# MelansonTech_Isolated_Shunt_Amplifier.net
KiCad netlist of a schematic drawn in Altium Designer
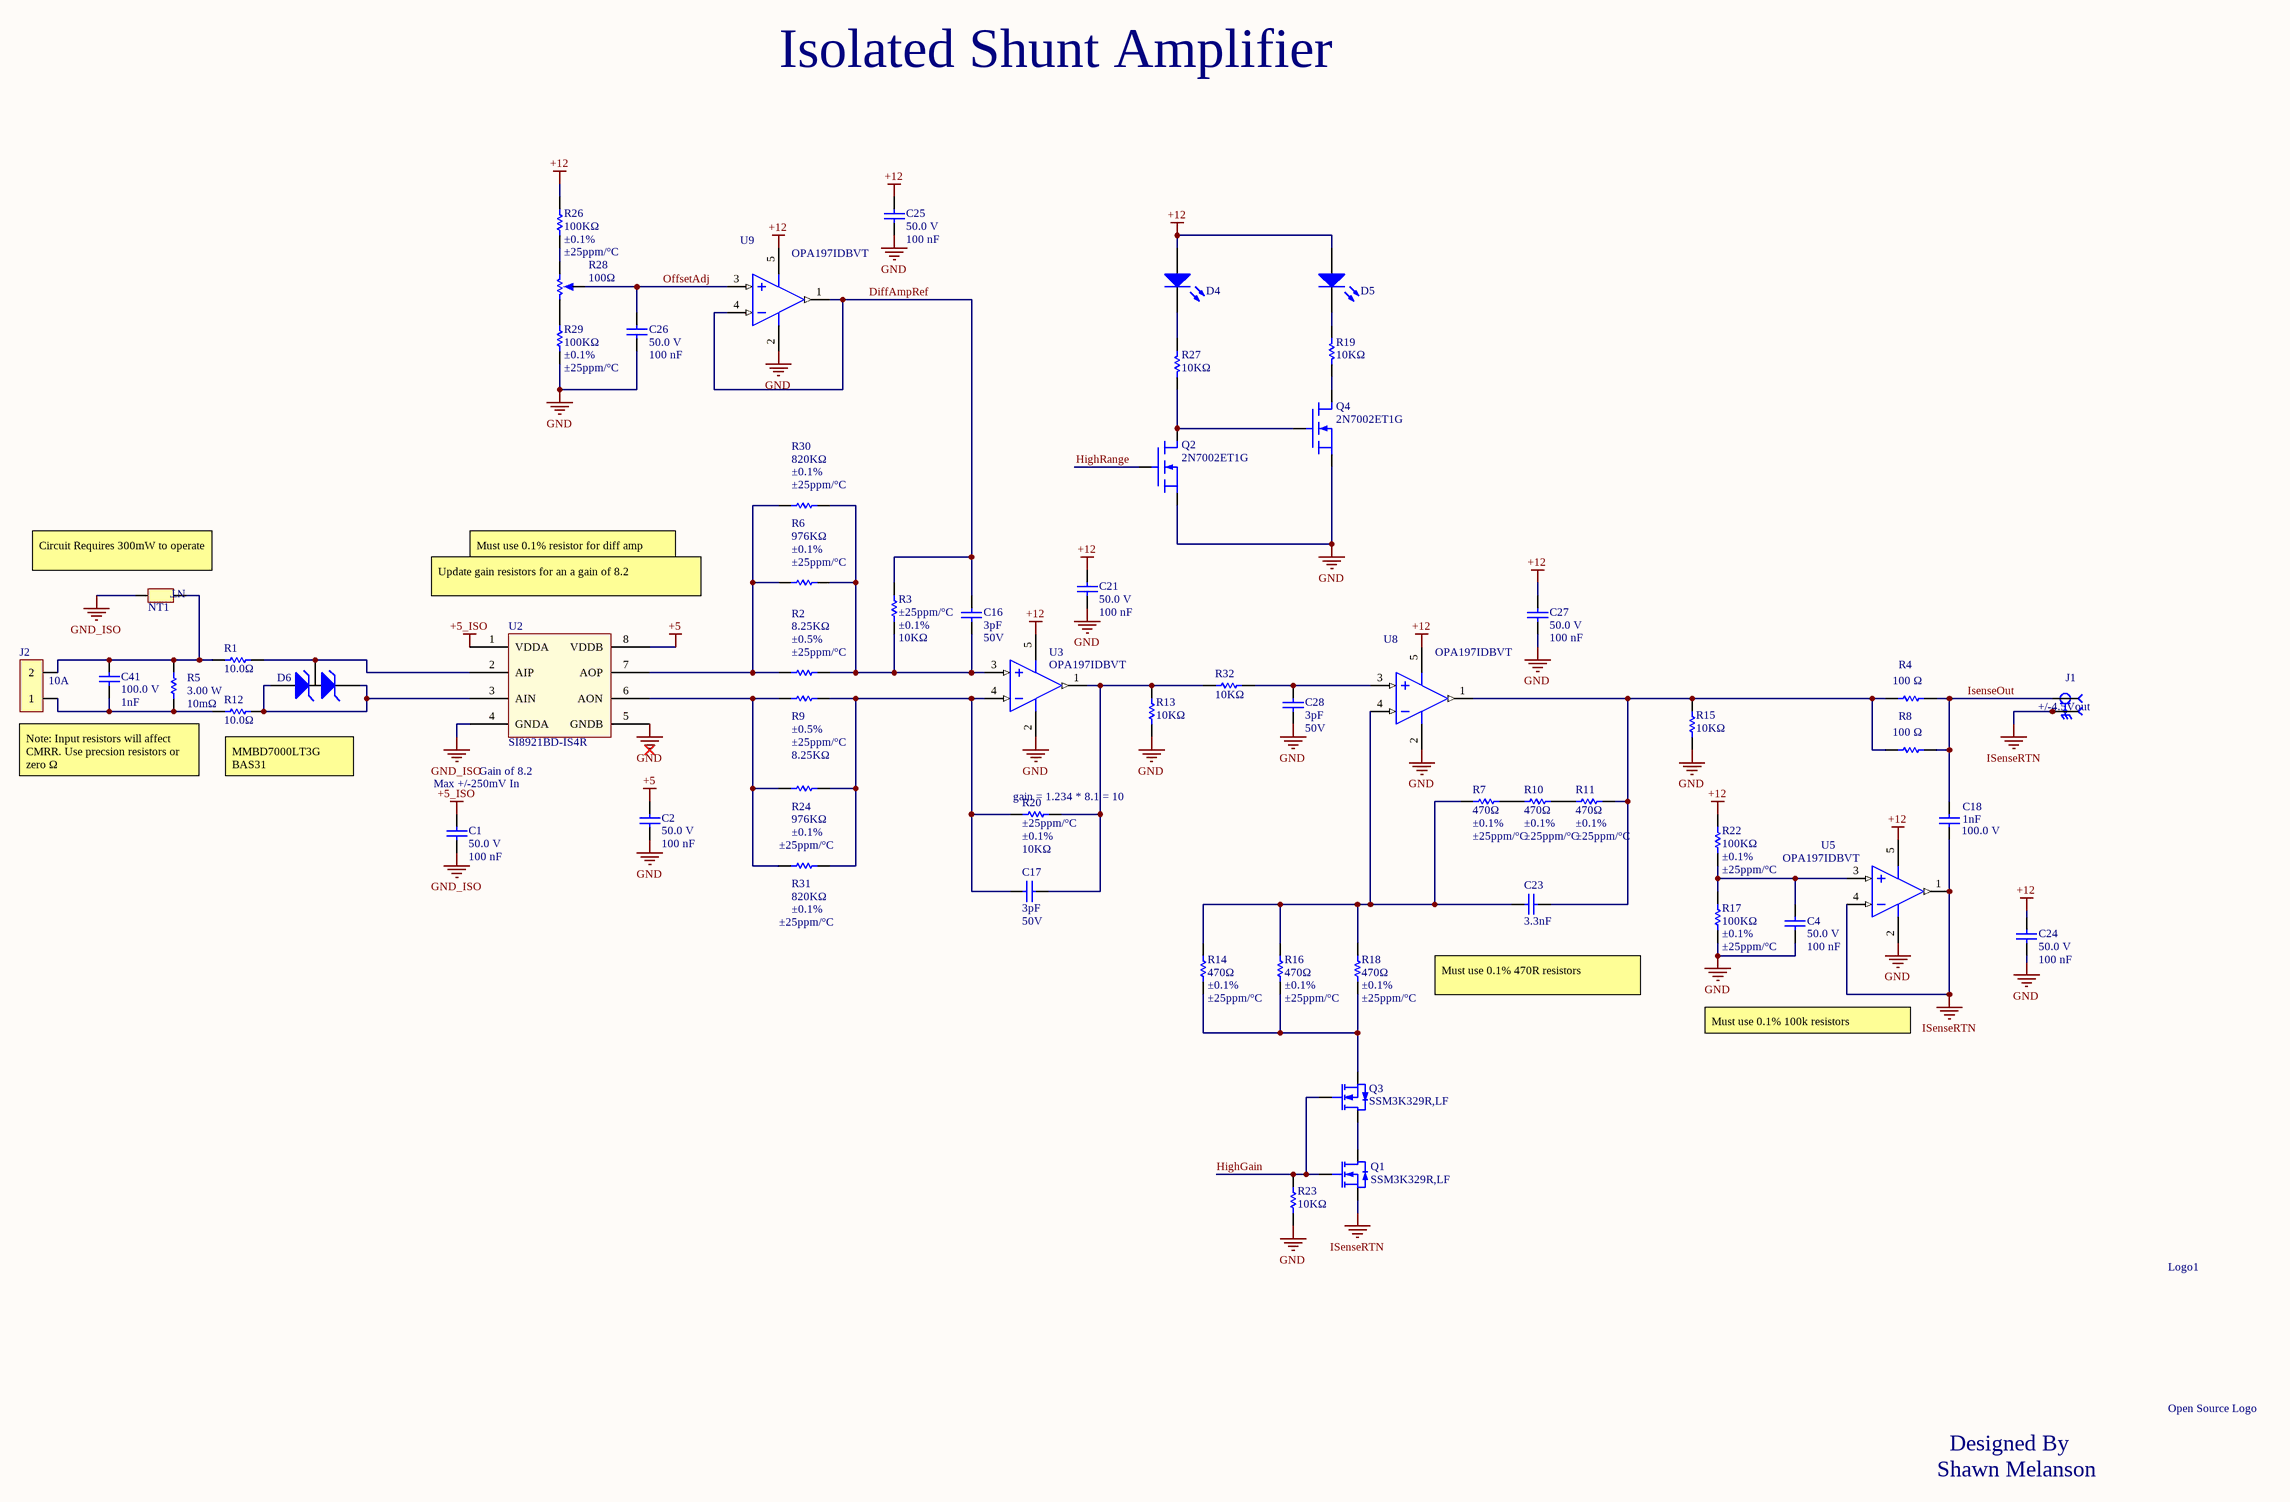
[diagram p0: MelansonTech Isolated Shunt Amplifier.SchDoc]

(export (version "E")
  (design (tool "Eeschema 10.0.6"))
  (components
    (comp (ref "C1")
      (value "CC0805KRX7R9BB104")
      (footprint "CAP, 0805, HD")
      (description "CAP CER 0.1UF 50V X7R 0805")
      (fields
        (field (name "VOLTAGE RATING (DC)") "50.0 V")
        (field (name "CAPACITANCE") "100 nF")
        (field (name "MANUFACTURER") "YAGEO")
      )
      (libsource (lib "Master Mar2024") (part "Cap,0805,100nf,50V,5%,CC0805KRX7R9BB104"))
    )
    (comp (ref "C2")
      (value "CC0805KRX7R9BB104")
      (footprint "CAP, 0805, HD")
      (description "CAP CER 0.1UF 50V X7R 0805")
      (fields
        (field (name "VOLTAGE RATING (DC)") "50.0 V")
        (field (name "CAPACITANCE") "100 nF")
        (field (name "MANUFACTURER") "YAGEO")
      )
      (libsource (lib "Master Mar2024") (part "Cap,0805,100nf,50V,5%,CC0805KRX7R9BB104"))
    )
    (comp (ref "C4")
      (value "CC0805KRX7R9BB104")
      (footprint "CAP, 0805, HD")
      (description "CAP CER 0.1UF 50V X7R 0805")
      (fields
        (field (name "VOLTAGE RATING (DC)") "50.0 V")
        (field (name "CAPACITANCE") "100 nF")
        (field (name "MANUFACTURER") "YAGEO")
      )
      (libsource (lib "Master Mar2024") (part "Cap,0805,100nf,50V,5%,CC0805KRX7R9BB104"))
    )
    (comp (ref "C16")
      (value "CC0805CRNPO9BN3R0")
      (footprint "CAP, 0805, HD")
      (description "CAP CER 3PF 50V C0G/NPO 0805")
      (fields
        (field (name "MANUFACTURER") "YAGEO")
        (field (name "TOLERANCE") "±0.25pF")
        (field (name "CAPACITANCE") "3pF")
        (field (name "VOLTAGE - RATED") "50V")
      )
      (libsource (lib "Master Mar2024") (part "CAP,0805,3pF,COG,NPO,CC0805CRNPO9BN3R0"))
    )
    (comp (ref "C17")
      (value "CC0805CRNPO9BN3R0")
      (footprint "CAP, 0805, HD")
      (description "CAP CER 3PF 50V C0G/NPO 0805")
      (fields
        (field (name "MANUFACTURER") "YAGEO")
        (field (name "TOLERANCE") "±0.25pF")
        (field (name "CAPACITANCE") "3pF")
        (field (name "VOLTAGE - RATED") "50V")
      )
      (libsource (lib "Master Mar2024") (part "CAP,0805,3pF,COG,NPO,CC0805CRNPO9BN3R0"))
    )
    (comp (ref "C18")
      (value "C0805X102J1GACAUTO")
      (footprint "CAP, 0805, HD")
      (description "CAPACITOR, 1NF, 100V, NP0, 0805")
      (fields (field (name "VOLTAGE RATING (DC)") "100.0 V") (field (name "CAPACITANCE") "1nF"))
      (libsource (lib "Master Nov2021") (part "Cap,0805,1nF,±5%,100Vdc,CL10F104ZB8NNNC"))
    )
    (comp (ref "C21")
      (value "CC0805KRX7R9BB104")
      (footprint "CAP, 0805, HD")
      (description "CAP CER 0.1UF 50V X7R 0805")
      (fields
        (field (name "VOLTAGE RATING (DC)") "50.0 V")
        (field (name "CAPACITANCE") "100 nF")
        (field (name "MANUFACTURER") "YAGEO")
      )
      (libsource (lib "Master Mar2024") (part "Cap,0805,100nf,50V,5%,CC0805KRX7R9BB104"))
    )
    (comp (ref "C23")
      (value "3.3nF")
      (footprint "CAP, 0805, HD")
      (libsource (lib "Master Mar2024") (part "CAP,0805,Generic"))
    )
    (comp (ref "C24")
      (value "CC0805KRX7R9BB104")
      (footprint "CAP, 0805, HD")
      (description "CAP CER 0.1UF 50V X7R 0805")
      (fields
        (field (name "VOLTAGE RATING (DC)") "50.0 V")
        (field (name "CAPACITANCE") "100 nF")
        (field (name "MANUFACTURER") "YAGEO")
      )
      (libsource (lib "Master Mar2024") (part "Cap,0805,100nf,50V,5%,CC0805KRX7R9BB104"))
    )
    (comp (ref "C25")
      (value "CC0805KRX7R9BB104")
      (footprint "CAP, 0805, HD")
      (description "CAP CER 0.1UF 50V X7R 0805")
      (fields
        (field (name "VOLTAGE RATING (DC)") "50.0 V")
        (field (name "CAPACITANCE") "100 nF")
        (field (name "MANUFACTURER") "YAGEO")
      )
      (libsource (lib "Master Mar2024") (part "Cap,0805,100nf,50V,5%,CC0805KRX7R9BB104"))
    )
    (comp (ref "C26")
      (value "CC0805KRX7R9BB104")
      (footprint "CAP, 0805, HD")
      (description "CAP CER 0.1UF 50V X7R 0805")
      (fields
        (field (name "VOLTAGE RATING (DC)") "50.0 V")
        (field (name "CAPACITANCE") "100 nF")
        (field (name "MANUFACTURER") "YAGEO")
      )
      (libsource (lib "Master Mar2024") (part "Cap,0805,100nf,50V,5%,CC0805KRX7R9BB104"))
    )
    (comp (ref "C27")
      (value "CC0805KRX7R9BB104")
      (footprint "CAP, 0805, HD")
      (description "CAP CER 0.1UF 50V X7R 0805")
      (fields
        (field (name "VOLTAGE RATING (DC)") "50.0 V")
        (field (name "CAPACITANCE") "100 nF")
        (field (name "MANUFACTURER") "YAGEO")
      )
      (libsource (lib "Master Mar2024") (part "Cap,0805,100nf,50V,5%,CC0805KRX7R9BB104"))
    )
    (comp (ref "C28")
      (value "CC0805CRNPO9BN3R0")
      (footprint "CAP, 0805, HD")
      (description "CAP CER 3PF 50V C0G/NPO 0805")
      (fields
        (field (name "MANUFACTURER") "YAGEO")
        (field (name "TOLERANCE") "±0.25pF")
        (field (name "CAPACITANCE") "3pF")
        (field (name "VOLTAGE - RATED") "50V")
      )
      (libsource (lib "Master Mar2024") (part "CAP,0805,3pF,COG,NPO,CC0805CRNPO9BN3R0"))
    )
    (comp (ref "C41")
      (value "C0805X102J1GACAUTO")
      (footprint "CAP, 0805, HD")
      (description "CAPACITOR, 1NF, 100V, NP0, 0805")
      (fields (field (name "VOLTAGE RATING (DC)") "100.0 V") (field (name "CAPACITANCE") "1nF"))
      (libsource (lib "Master Nov2021") (part "Cap,0805,1nF,±5%,100Vdc,CL10F104ZB8NNNC"))
    )
    (comp (ref "D4")
      (value "OVLBB4C7")
      (footprint "LED,TH,T1,3MM-Vert")
      (description "Blue 470nm LED Indication - Discrete 3.2V Radial")
      (fields (field (name "MFG") "TT Electronics/Optek Technology"))
      (libsource (lib "Master Nov2021") (part "LED,TH,T1,3mm,Blue,OVLBB4C7"))
    )
    (comp (ref "D5")
      (value "OVLBB4C7")
      (footprint "LED,TH,T1,3MM-Vert")
      (description "Blue 470nm LED Indication - Discrete 3.2V Radial")
      (fields (field (name "MFG") "TT Electronics/Optek Technology"))
      (libsource (lib "Master Nov2021") (part "LED,TH,T1,3mm,Blue,OVLBB4C7"))
    )
    (comp (ref "D6")
      (value "BAT54SLT1G")
      (footprint "SOT23-3")
      (fields (field (name "BASE PART NUMBER") "BAT54SL") (field (name "MANUFACTURER") "ON Semiconductor"))
      (libsource (lib "Master Nov2021") (part "Diode,Shottky,Array,Series,30V,200mA,BAT54SLT1G"))
    )
    (comp (ref "J1")
      (value "142-0701-801")
      (footprint "CINCH_142-0701-801")
      (description "CONN SMA JACK STR 50OHM EDGE MNT")
      (fields (field (name "MANUFACTURER") "Cinch Connectivity Solutions Johnson"))
      (libsource (lib "Master JUL_2019-Shawn") (part "Conn,SMA,Female,End Launch,142-0701-801"))
    )
    (comp (ref "J2")
      (value "TE Connectivity 282836-2")
      (footprint "TERM BLOCK 2POS SIDE ENTRY 5MM")
      (description "Wire to Board 2 Position 5 mm Pitch 30-16 AWG Euro Style Terminal Block")
      (fields (field (name "MANUFACTURER PART NUMBER") "282836-2"))
      (libsource (lib "Master DEC 2020") (part "TERM BLOCK 2POS SIDE ENTRY 5MM, 282836-2"))
    )
    (comp (ref "Logo1")
      (value "Open Source Logo")
      (footprint "Symbol,Open Source - No Text")
      (description "Open Source Silk Screen Logo")
      (libsource (lib "Master Nov2021") (part "Symbol,Open Source"))
    )
    (comp (ref "NT1")
      (value "Net Tie,0.254mm")
      (footprint "0.254mm Net Tie")
      (libsource (lib "Master Mar2021") (part "Net Tie,0.254mm"))
    )
    (comp (ref "Q1")
      (value "SSM3K329R,LF")
      (footprint "SOT23-3")
      (description "N-Channel 30V 3.5A (Ta) 1W (Ta) Surface Mount SOT-23F")
      (fields (field (name "MFG P/N") "SSM3K329R,LF"))
      (libsource (lib "Master Mar2024") (part "MOSFET.N-Chan, SOT-23-3,3.5A,30V,1W,SSM3K329R,LF"))
    )
    (comp (ref "Q2")
      (value "2N7002ET1G")
      (footprint "SOT23-3")
      (description "Small Signal MOSFET, 60 V, 310 mA, Single, N-Channel, 3-Pin SOT-23, Pb-Free, Tape and Reel")
      (fields
        (field (name "MANUFACTURER") "ON Semiconductor")
        (field (name "MANUFACTURER PART NUMBER") "2N7002ET1G")
      )
      (libsource (lib "Master DEC 2020") (part "MOSFET,N-Channel,SOT23,0.25A,60V,2N7002ET1G"))
    )
    (comp (ref "Q3")
      (value "SSM3K329R,LF")
      (footprint "SOT23-3")
      (description "N-Channel 30V 3.5A (Ta) 1W (Ta) Surface Mount SOT-23F")
      (fields (field (name "MFG P/N") "SSM3K329R,LF"))
      (libsource (lib "Master Mar2024") (part "MOSFET.N-Chan, SOT-23-3,3.5A,30V,1W,SSM3K329R,LF"))
    )
    (comp (ref "Q4")
      (value "2N7002ET1G")
      (footprint "SOT23-3")
      (description "Small Signal MOSFET, 60 V, 310 mA, Single, N-Channel, 3-Pin SOT-23, Pb-Free, Tape and Reel")
      (fields
        (field (name "MANUFACTURER") "ON Semiconductor")
        (field (name "MANUFACTURER PART NUMBER") "2N7002ET1G")
      )
      (libsource (lib "Master DEC 2020") (part "MOSFET,N-Channel,SOT23,0.25A,60V,2N7002ET1G"))
    )
    (comp (ref "R1")
      (value "Vishay CRCW08051K00JNEA")
      (footprint "res, 0805, HD")
      (description "RES 10 OHM 5% 1/8W 0805")
      (fields
        (field (name "MANUFACTURER") "Stackpole Electronics Inc")
        (field (name "TOLERANCE") "±5%")
        (field (name "RESISTANCE") "10.0Ω")
      )
      (libsource (lib "Master Nov2021") (part "Res,0805,10.0Ω,5%,±200ppm/°C,RMCF0805JT10R0"))
    )
    (comp (ref "R2")
      (value "RR1220P-8251-D-M")
      (footprint "res, 0805, HD")
      (description "RES SMD 8.25KOHM 0.5% 1/10W 0805")
      (fields
        (field (name "MANUFACTURER") "Susumu")
        (field (name "TOLERANCE") "±0.5%")
        (field (name "TEMPERATURE COEFFICIENT") "±25ppm/°C")
        (field (name "RESISTANCE") "8.25KΩ")
      )
      (libsource (lib "Master Mar2024") (part "Res,0805,8.25KΩ,0.5%,±25ppm/°C,RR1220P-8251-D-M"))
    )
    (comp (ref "R3")
      (value "RG2012P-103-B-T5")
      (footprint "res, 0805, HD")
      (description "RES SMD 10K OHM 0.1% 1/8W 0805")
      (fields
        (field (name "MFR") "Susumu")
        (field (name "TEMPERATURE COEFFICIENT") "±25ppm/°C")
        (field (name "RESISTANCE TOLERANCE") "±0.1%")
        (field (name "RESISTANCE") "10KΩ")
      )
      (libsource (lib "Master Mar2024") (part "Res,0805,10.0kΩ,0.1%,±25ppm/°C,RG2012P-103-B-T5"))
    )
    (comp (ref "R4")
      (value "CRCW0805100RJNEAC")
      (footprint "res, 0805, HD")
      (description "RES 100 OHM 5% 1/8W 0805")
      (fields (field (name "TOLERANCE") "±5%") (field (name "RESISTANCE") "100 Ω"))
      (libsource (lib "Master Mar2024") (part "Res,0805,100Ω,5%,±200ppm/°C"))
    )
    (comp (ref "R5")
      (value "CRA2512-FZ-R010ELF")
      (footprint "Res 2512")
      (description "Resistor; Metal Film; Res 0.01 Ohms; Pwr-Rtg 3 W; Tol 1%; SMT; 2512; Current Sense")
      (fields (field (name "POWER RATING") "3.00 W") (field (name "RESISTANCE") "10mΩ"))
      (libsource (lib "Master Mar2024") (part "Res,2512,10mΩ,3.00W,±1%,CRA2512-FZ-R010ELF"))
    )
    (comp (ref "R6")
      (value "ERA-6AEB9763V")
      (footprint "res, 0805, HD")
      (description "RES SMD 976K OHM 0.1% 1/8W 0805")
      (fields
        (field (name "MANUFACTURER") "Panasonic Electronic Components")
        (field (name "RESISTANCE") "976KΩ")
        (field (name "TOLERANCE") "±0.1%")
        (field (name "TEMPERATURE COEFFICIENT") "±25ppm/°C")
      )
      (libsource (lib "Master Mar2024") (part "Res,0805,976KΩ,±0.1%,±25ppm/°C,ERA-6AEB9763V"))
    )
    (comp (ref "R7")
      (value "ERA-6AEB471V")
      (footprint "res, 0805, HD")
      (description "RES SMD 470 OHM 0.1% 1/8W 0805")
      (fields
        (field (name "MANUFACTURER") "Panasonic Electronic Components")
        (field (name "RESISTANCE") "470Ω")
        (field (name "TOLERANCE") "±0.1%")
        (field (name "TEMPERATURE COEFFICIENT") "±25ppm/°C")
      )
      (libsource (lib "Master Mar2024") (part "Res,0805,470Ω,±0.1%,±25ppm/°C,ERA-6AEB471V"))
    )
    (comp (ref "R8")
      (value "CRCW0805100RJNEAC")
      (footprint "res, 0805, HD")
      (description "RES 100 OHM 5% 1/8W 0805")
      (fields (field (name "TOLERANCE") "±5%") (field (name "RESISTANCE") "100 Ω"))
      (libsource (lib "Master Mar2024") (part "Res,0805,100Ω,5%,±200ppm/°C"))
    )
    (comp (ref "R9")
      (value "RR1220P-8251-D-M")
      (footprint "res, 0805, HD")
      (description "RES SMD 8.25KOHM 0.5% 1/10W 0805")
      (fields
        (field (name "MANUFACTURER") "Susumu")
        (field (name "TOLERANCE") "±0.5%")
        (field (name "TEMPERATURE COEFFICIENT") "±25ppm/°C")
        (field (name "RESISTANCE") "8.25KΩ")
      )
      (libsource (lib "Master Mar2024") (part "Res,0805,8.25KΩ,0.5%,±25ppm/°C,RR1220P-8251-D-M"))
    )
    (comp (ref "R10")
      (value "ERA-6AEB471V")
      (footprint "res, 0805, HD")
      (description "RES SMD 470 OHM 0.1% 1/8W 0805")
      (fields
        (field (name "MANUFACTURER") "Panasonic Electronic Components")
        (field (name "RESISTANCE") "470Ω")
        (field (name "TOLERANCE") "±0.1%")
        (field (name "TEMPERATURE COEFFICIENT") "±25ppm/°C")
      )
      (libsource (lib "Master Mar2024") (part "Res,0805,470Ω,±0.1%,±25ppm/°C,ERA-6AEB471V"))
    )
    (comp (ref "R11")
      (value "ERA-6AEB471V")
      (footprint "res, 0805, HD")
      (description "RES SMD 470 OHM 0.1% 1/8W 0805")
      (fields
        (field (name "MANUFACTURER") "Panasonic Electronic Components")
        (field (name "RESISTANCE") "470Ω")
        (field (name "TOLERANCE") "±0.1%")
        (field (name "TEMPERATURE COEFFICIENT") "±25ppm/°C")
      )
      (libsource (lib "Master Mar2024") (part "Res,0805,470Ω,±0.1%,±25ppm/°C,ERA-6AEB471V"))
    )
    (comp (ref "R12")
      (value "Vishay / Dale CRCW080510K0FKTA")
      (footprint "res, 0805, HD")
      (description "RES 10 OHM 5% 1/8W 0805")
      (fields
        (field (name "MANUFACTURER") "Stackpole Electronics Inc")
        (field (name "TOLERANCE") "±5%")
        (field (name "RESISTANCE") "10.0Ω")
      )
      (libsource (lib "Master Nov2021") (part "Res,0805,10.0Ω,5%,±200ppm/°C,RMCF0805JT10R0"))
    )
    (comp (ref "R13")
      (value "Vishay / Dale CRCW080510K0FKTA")
      (footprint "res, 0805, HD")
      (description "RES SMD 10K OHM 1% 1/8W 0805")
      (fields (field (name "RESISTANCE") "10KΩ"))
      (libsource (lib "Master DEC 2020") (part "Res,0805,10.0kΩ,1%,100 ppm,CRCW080510K0FKTA"))
    )
    (comp (ref "R14")
      (value "ERA-6AEB471V")
      (footprint "res, 0805, HD")
      (description "RES SMD 470 OHM 0.1% 1/8W 0805")
      (fields
        (field (name "MANUFACTURER") "Panasonic Electronic Components")
        (field (name "RESISTANCE") "470Ω")
        (field (name "TOLERANCE") "±0.1%")
        (field (name "TEMPERATURE COEFFICIENT") "±25ppm/°C")
      )
      (libsource (lib "Master Mar2024") (part "Res,0805,470Ω,±0.1%,±25ppm/°C,ERA-6AEB471V"))
    )
    (comp (ref "R15")
      (value "Vishay / Dale CRCW080510K0FKTA")
      (footprint "res, 0805, HD")
      (description "RES SMD 10K OHM 1% 1/8W 0805")
      (fields (field (name "RESISTANCE") "10KΩ"))
      (libsource (lib "Master JULY2019") (part "Res,0805,10.0kΩ,1%,100 ppm,CRCW080510K0FKTA"))
    )
    (comp (ref "R16")
      (value "ERA-6AEB471V")
      (footprint "res, 0805, HD")
      (description "RES SMD 470 OHM 0.1% 1/8W 0805")
      (fields
        (field (name "MANUFACTURER") "Panasonic Electronic Components")
        (field (name "RESISTANCE") "470Ω")
        (field (name "TOLERANCE") "±0.1%")
        (field (name "TEMPERATURE COEFFICIENT") "±25ppm/°C")
      )
      (libsource (lib "Master Mar2024") (part "Res,0805,470Ω,±0.1%,±25ppm/°C,ERA-6AEB471V"))
    )
    (comp (ref "R17")
      (value "ERA-6AEB104V")
      (footprint "res, 0805, HD")
      (description "RES SMD 100K OHM 0.1% 1/8W 0805")
      (fields
        (field (name "MANUFACTURER") "Panasonic Electronic Components")
        (field (name "RESISTANCE") "100KΩ")
        (field (name "TOLERANCE") "±0.1%")
        (field (name "TEMPERATURE COEFFICIENT") "±25ppm/°C")
      )
      (libsource (lib "Master Mar2024") (part "Res,0805,100K,±0.1%,±25ppm/°C,ERA-6AEB104V"))
    )
    (comp (ref "R18")
      (value "ERA-6AEB471V")
      (footprint "res, 0805, HD")
      (description "RES SMD 470 OHM 0.1% 1/8W 0805")
      (fields
        (field (name "MANUFACTURER") "Panasonic Electronic Components")
        (field (name "RESISTANCE") "470Ω")
        (field (name "TOLERANCE") "±0.1%")
        (field (name "TEMPERATURE COEFFICIENT") "±25ppm/°C")
      )
      (libsource (lib "Master Mar2024") (part "Res,0805,470Ω,±0.1%,±25ppm/°C,ERA-6AEB471V"))
    )
    (comp (ref "R19")
      (value "Vishay / Dale CRCW080510K0FKTA")
      (footprint "res, 0805, HD")
      (description "RES SMD 10K OHM 1% 1/8W 0805")
      (fields (field (name "RESISTANCE") "10KΩ"))
      (libsource (lib "Master JULY2019") (part "Res,0805,10.0kΩ,1%,100 ppm,CRCW080510K0FKTA"))
    )
    (comp (ref "R20")
      (value "RG2012P-103-B-T5")
      (footprint "res, 0805, HD")
      (description "RES SMD 10K OHM 0.1% 1/8W 0805")
      (fields
        (field (name "MFR") "Susumu")
        (field (name "TEMPERATURE COEFFICIENT") "±25ppm/°C")
        (field (name "RESISTANCE TOLERANCE") "±0.1%")
        (field (name "RESISTANCE") "10KΩ")
      )
      (libsource (lib "Master Mar2024") (part "Res,0805,10.0kΩ,0.1%,±25ppm/°C,RG2012P-103-B-T5"))
    )
    (comp (ref "R22")
      (value "ERA-6AEB104V")
      (footprint "res, 0805, HD")
      (description "RES SMD 100K OHM 0.1% 1/8W 0805")
      (fields
        (field (name "MANUFACTURER") "Panasonic Electronic Components")
        (field (name "RESISTANCE") "100KΩ")
        (field (name "TOLERANCE") "±0.1%")
        (field (name "TEMPERATURE COEFFICIENT") "±25ppm/°C")
      )
      (libsource (lib "Master Mar2024") (part "Res,0805,100K,±0.1%,±25ppm/°C,ERA-6AEB104V"))
    )
    (comp (ref "R23")
      (value "Vishay / Dale CRCW080510K0FKTA")
      (footprint "res, 0805, HD")
      (description "RES SMD 10K OHM 1% 1/8W 0805")
      (fields (field (name "RESISTANCE") "10KΩ"))
      (libsource (lib "Master JULY2019") (part "Res,0805,10.0kΩ,1%,100 ppm,CRCW080510K0FKTA"))
    )
    (comp (ref "R24")
      (value "ERA-6AEB9763V")
      (footprint "res, 0805, HD")
      (description "RES SMD 976K OHM 0.1% 1/8W 0805")
      (fields
        (field (name "MANUFACTURER") "Panasonic Electronic Components")
        (field (name "RESISTANCE") "976KΩ")
        (field (name "TOLERANCE") "±0.1%")
        (field (name "TEMPERATURE COEFFICIENT") "±25ppm/°C")
      )
      (libsource (lib "Master Mar2024") (part "Res,0805,976KΩ,±0.1%,±25ppm/°C,ERA-6AEB9763V"))
    )
    (comp (ref "R26")
      (value "ERA-6AEB104V")
      (footprint "res, 0805, HD")
      (description "RES SMD 100K OHM 0.1% 1/8W 0805")
      (fields
        (field (name "MANUFACTURER") "Panasonic Electronic Components")
        (field (name "RESISTANCE") "100KΩ")
        (field (name "TOLERANCE") "±0.1%")
        (field (name "TEMPERATURE COEFFICIENT") "±25ppm/°C")
      )
      (libsource (lib "Master Mar2024") (part "Res,0805,100K,±0.1%,±25ppm/°C,ERA-6AEB104V"))
    )
    (comp (ref "R27")
      (value "Vishay / Dale CRCW080510K0FKTA")
      (footprint "res, 0805, HD")
      (description "RES SMD 10K OHM 1% 1/8W 0805")
      (fields (field (name "RESISTANCE") "10KΩ"))
      (libsource (lib "Master JULY2019") (part "Res,0805,10.0kΩ,1%,100 ppm,CRCW080510K0FKTA"))
    )
    (comp (ref "R28")
      (value "TC33X-2-101E")
      (footprint "Res,SMD,POT,TC33 Series")
      (description "TRIMMER 100 OHM 0.1W J LEAD TOP")
      (fields
        (field (name "MANUFACTURER") "Bourns Inc.")
        (field (name "TOLERANCE") "±25%")
        (field (name "RESISTANCE") "100Ω")
      )
      (libsource (lib "Master Nov2021") (part "Res,POT,SMD,100Ω,0.1W, TC33X-2-101E"))
    )
    (comp (ref "R29")
      (value "ERA-6AEB104V")
      (footprint "res, 0805, HD")
      (description "RES SMD 100K OHM 0.1% 1/8W 0805")
      (fields
        (field (name "MANUFACTURER") "Panasonic Electronic Components")
        (field (name "RESISTANCE") "100KΩ")
        (field (name "TOLERANCE") "±0.1%")
        (field (name "TEMPERATURE COEFFICIENT") "±25ppm/°C")
      )
      (libsource (lib "Master Mar2024") (part "Res,0805,100K,±0.1%,±25ppm/°C,ERA-6AEB104V"))
    )
    (comp (ref "R30")
      (value "RG2012P-824-D-T5")
      (footprint "res, 0805, HD")
      (description "RES SMD 820K OHM 0.5% 1/8W 0805")
      (fields
        (field (name "MANUFACTURER") "Susumu")
        (field (name "RESISTANCE") "820KΩ")
        (field (name "TOLERANCE") "±0.1%")
        (field (name "TEMPERATURE COEFFICIENT") "±25ppm/°C")
      )
      (libsource (lib "Master Mar2024") (part "Res,0805,820KΩ,±0.1%,±25ppm/°C,RG2012P-824-D-T5"))
    )
    (comp (ref "R31")
      (value "RG2012P-824-D-T5")
      (footprint "res, 0805, HD")
      (description "RES SMD 820K OHM 0.5% 1/8W 0805")
      (fields
        (field (name "MANUFACTURER") "Susumu")
        (field (name "RESISTANCE") "820KΩ")
        (field (name "TOLERANCE") "±0.1%")
        (field (name "TEMPERATURE COEFFICIENT") "±25ppm/°C")
      )
      (libsource (lib "Master Mar2024") (part "Res,0805,820KΩ,±0.1%,±25ppm/°C,RG2012P-824-D-T5"))
    )
    (comp (ref "R32")
      (value "CRCW080510K0FKTA")
      (footprint "res, 0805, HD")
      (description "RES SMD 10K OHM 1% 1/8W 0805")
      (fields (field (name "RESISTANCE") "10KΩ"))
      (libsource (lib "Master Mar2024") (part "Res,0805,10.0kΩ,1%,100 ppm,CRCW080510K0FKTA"))
    )
    (comp (ref "U2")
      (value "SI8921BD-IS4R")
      (footprint "SOIC-8 DWV")
      (description "Isolation IC Inverters, Power Supplies, UPS 8-SOIC")
      (fields (field (name "MFR") "Skyworks Solutions Inc."))
      (libsource (lib "Master Mar2024") (part "IC,CurrentSense,Isolated,8.2 Gain,500Khz,SI8921BD-IS4R"))
    )
    (comp (ref "U3")
      (value "OPA197IDBVT")
      (footprint "SOT23-5")
      (description "General Purpose Amplifier 1 Circuit Rail-to-Rail SOT-23-5")
      (fields (field (name "MANUFACTURER") "Texas Instruments") (field (name "MFG P/N") "OPA197IDBVT"))
      (libsource (lib "Master JULY2019") (part "OPAMP, single, General Purpose,Rail-to-Rail,10MHz,SOT-23-5,OPA197IDBVT"))
    )
    (comp (ref "U5")
      (value "OPA197IDBVT")
      (footprint "SOT23-5")
      (description "General Purpose Amplifier 1 Circuit Rail-to-Rail SOT-23-5")
      (fields (field (name "MANUFACTURER") "Texas Instruments") (field (name "MFG P/N") "OPA197IDBVT"))
      (libsource (lib "Master JULY2019") (part "OPAMP, single, General Purpose,Rail-to-Rail,10MHz,SOT-23-5,OPA197IDBVT"))
    )
    (comp (ref "U8")
      (value "OPA197IDBVT")
      (footprint "SOT23-5")
      (description "General Purpose Amplifier 1 Circuit Rail-to-Rail SOT-23-5")
      (fields (field (name "MANUFACTURER") "Texas Instruments") (field (name "MFG P/N") "OPA197IDBVT"))
      (libsource (lib "Master JULY2019") (part "OPAMP, single, General Purpose,Rail-to-Rail,10MHz,SOT-23-5,OPA197IDBVT"))
    )
    (comp (ref "U9")
      (value "OPA197IDBVT")
      (footprint "SOT23-5")
      (description "General Purpose Amplifier 1 Circuit Rail-to-Rail SOT-23-5")
      (fields (field (name "MANUFACTURER") "Texas Instruments") (field (name "MFG P/N") "OPA197IDBVT"))
      (libsource (lib "Master JULY2019") (part "OPAMP, single, General Purpose,Rail-to-Rail,10MHz,SOT-23-5,OPA197IDBVT"))
    )
  )
  (nets
    (net (code "1") (name "+5") (class "Default")
      (node (ref "C2") (pin "2") (pinfunction "2_2") (pintype "passive"))
      (node (ref "U2") (pin "8") (pinfunction "VDDB_8") (pintype "passive"))
    )
    (net (code "2") (name "+5_ISO") (class "Default")
      (node (ref "C1") (pin "2") (pinfunction "2_2") (pintype "passive"))
      (node (ref "U2") (pin "1") (pinfunction "VDDA_1") (pintype "passive"))
    )
    (net (code "3") (name "+12") (class "Default")
      (node (ref "C21") (pin "2") (pinfunction "2_2") (pintype "passive"))
      (node (ref "C24") (pin "2") (pinfunction "2_2") (pintype "passive"))
      (node (ref "C25") (pin "2") (pinfunction "2_2") (pintype "passive"))
      (node (ref "C27") (pin "2") (pinfunction "2_2") (pintype "passive"))
      (node (ref "D4") (pin "1") (pinfunction "A_1") (pintype "passive"))
      (node (ref "D5") (pin "1") (pinfunction "A_1") (pintype "passive"))
      (node (ref "R22") (pin "2") (pinfunction "2_2") (pintype "passive"))
      (node (ref "R26") (pin "2") (pinfunction "2_2") (pintype "passive"))
      (node (ref "U3") (pin "5") (pinfunction "V+_5") (pintype "power_in"))
      (node (ref "U5") (pin "5") (pinfunction "V+_5") (pintype "power_in"))
      (node (ref "U8") (pin "5") (pinfunction "V+_5") (pintype "power_in"))
      (node (ref "U9") (pin "5") (pinfunction "V+_5") (pintype "power_in"))
    )
    (net (code "4") (name "/DiffAmpRef") (class "Default")
      (node (ref "C16") (pin "1") (pinfunction "1_1") (pintype "passive"))
      (node (ref "R3") (pin "1") (pinfunction "1_1") (pintype "passive"))
      (node (ref "U9") (pin "1") (pinfunction "1OUT_1") (pintype "output"))
      (node (ref "U9") (pin "4") (pinfunction "1IN-_4") (pintype "input"))
    )
    (net (code "5") (name "/HighGain") (class "Default")
      (node (ref "Q1") (pin "1") (pinfunction "G_1") (pintype "passive"))
      (node (ref "Q3") (pin "1") (pinfunction "G_1") (pintype "passive"))
      (node (ref "R23") (pin "1") (pinfunction "1_1") (pintype "passive"))
    )
    (net (code "6") (name "/HighRange") (class "Default")
      (node (ref "Q2") (pin "1") (pinfunction "G_1") (pintype "passive"))
    )
    (net (code "7") (name "/IsenseOut") (class "Default")
      (node (ref "C18") (pin "2") (pinfunction "2_2") (pintype "passive"))
      (node (ref "J1") (pin "1") (pinfunction "1_1") (pintype "passive"))
      (node (ref "R4") (pin "1") (pinfunction "1_1") (pintype "passive"))
      (node (ref "R8") (pin "1") (pinfunction "1_1") (pintype "passive"))
    )
    (net (code "8") (name "/OffsetAdj") (class "Default")
      (node (ref "C26") (pin "2") (pinfunction "2_2") (pintype "passive"))
      (node (ref "R28") (pin "2") (pinfunction "2_2") (pintype "passive"))
      (node (ref "U9") (pin "3") (pinfunction "1IN+_3") (pintype "input"))
    )
    (net (code "9") (name "GND") (class "Default")
      (node (ref "C2") (pin "1") (pinfunction "1_1") (pintype "passive"))
      (node (ref "C21") (pin "1") (pinfunction "1_1") (pintype "passive"))
      (node (ref "C24") (pin "1") (pinfunction "1_1") (pintype "passive"))
      (node (ref "C25") (pin "1") (pinfunction "1_1") (pintype "passive"))
      (node (ref "C26") (pin "1") (pinfunction "1_1") (pintype "passive"))
      (node (ref "C27") (pin "1") (pinfunction "1_1") (pintype "passive"))
      (node (ref "C28") (pin "1") (pinfunction "1_1") (pintype "passive"))
      (node (ref "C4") (pin "1") (pinfunction "1_1") (pintype "passive"))
      (node (ref "Q2") (pin "2") (pinfunction "S_2") (pintype "passive"))
      (node (ref "Q4") (pin "2") (pinfunction "S_2") (pintype "passive"))
      (node (ref "R13") (pin "2") (pinfunction "2_2") (pintype "passive"))
      (node (ref "R15") (pin "1") (pinfunction "1_1") (pintype "passive"))
      (node (ref "R17") (pin "1") (pinfunction "1_1") (pintype "passive"))
      (node (ref "R23") (pin "2") (pinfunction "2_2") (pintype "passive"))
      (node (ref "R29") (pin "1") (pinfunction "1_1") (pintype "passive"))
      (node (ref "U2") (pin "5") (pinfunction "GNDB_5") (pintype "passive"))
      (node (ref "U3") (pin "2") (pinfunction "V-_2") (pintype "power_in"))
      (node (ref "U5") (pin "2") (pinfunction "V-_2") (pintype "power_in"))
      (node (ref "U8") (pin "2") (pinfunction "V-_2") (pintype "power_in"))
      (node (ref "U9") (pin "2") (pinfunction "V-_2") (pintype "power_in"))
    )
    (net (code "10") (name "GND_ISO") (class "Default")
      (node (ref "C1") (pin "1") (pinfunction "1_1") (pintype "passive"))
      (node (ref "NT1") (pin "2") (pinfunction "2_2") (pintype "passive"))
      (node (ref "U2") (pin "4") (pinfunction "GNDA_4") (pintype "passive"))
    )
    (net (code "11") (name "ISenseRTN") (class "Default")
      (node (ref "C18") (pin "1") (pinfunction "1_1") (pintype "passive"))
      (node (ref "J1") (pin "S1") (pinfunction "2_S1") (pintype "passive"))
      (node (ref "J1") (pin "S2") (pinfunction "2_S2") (pintype "passive"))
      (node (ref "J1") (pin "S3") (pinfunction "2_S3") (pintype "passive"))
      (node (ref "J1") (pin "S4") (pinfunction "2_S4") (pintype "passive"))
      (node (ref "Q1") (pin "2") (pinfunction "S_2") (pintype "passive"))
      (node (ref "U5") (pin "1") (pinfunction "1OUT_1") (pintype "output"))
      (node (ref "U5") (pin "4") (pinfunction "1IN-_4") (pintype "input"))
    )
    (net (code "12") (name "Net-(C41-Pad1)") (class "Default")
      (node (ref "C41") (pin "1") (pinfunction "1_1") (pintype "passive"))
      (node (ref "J2") (pin "1") (pinfunction "1_1") (pintype "passive"))
      (node (ref "R12") (pin "2") (pinfunction "2_2") (pintype "passive"))
      (node (ref "R5") (pin "2") (pinfunction "2_2") (pintype "passive"))
    )
    (net (code "13") (name "Net-(C41-Pad2)") (class "Default")
      (node (ref "C41") (pin "2") (pinfunction "2_2") (pintype "passive"))
      (node (ref "J2") (pin "2") (pinfunction "2_2") (pintype "passive"))
      (node (ref "NT1") (pin "1") (pinfunction "1_1") (pintype "passive"))
      (node (ref "R1") (pin "2") (pinfunction "2_2") (pintype "passive"))
      (node (ref "R5") (pin "1") (pinfunction "1_1") (pintype "passive"))
    )
    (net (code "14") (name "Net-(D4-K)") (class "Default")
      (node (ref "D4") (pin "2") (pinfunction "K_2") (pintype "passive"))
      (node (ref "R27") (pin "1") (pinfunction "1_1") (pintype "passive"))
    )
    (net (code "15") (name "Net-(D5-K)") (class "Default")
      (node (ref "D5") (pin "2") (pinfunction "K_2") (pintype "passive"))
      (node (ref "R19") (pin "1") (pinfunction "1_1") (pintype "passive"))
    )
    (net (code "16") (name "Net-(D6-A)") (class "Default")
      (node (ref "D6") (pin "1") (pinfunction "A_1") (pintype "passive"))
      (node (ref "D6") (pin "2") (pinfunction "K_2") (pintype "passive"))
      (node (ref "R12") (pin "1") (pinfunction "1_1") (pintype "passive"))
      (node (ref "U2") (pin "3") (pinfunction "AIN_3") (pintype "passive"))
    )
    (net (code "17") (name "Net-(D6-AK)") (class "Default")
      (node (ref "D6") (pin "3") (pinfunction "AK_3") (pintype "passive"))
      (node (ref "R1") (pin "1") (pinfunction "1_1") (pintype "passive"))
      (node (ref "U2") (pin "2") (pinfunction "AIP_2") (pintype "passive"))
    )
    (net (code "18") (name "Net-(Q1-D)") (class "Default")
      (node (ref "Q1") (pin "3") (pinfunction "D_3") (pintype "passive"))
      (node (ref "Q3") (pin "3") (pinfunction "D_3") (pintype "passive"))
    )
    (net (code "19") (name "Net-(Q2-D)") (class "Default")
      (node (ref "Q2") (pin "3") (pinfunction "D_3") (pintype "passive"))
      (node (ref "Q4") (pin "1") (pinfunction "G_1") (pintype "passive"))
      (node (ref "R27") (pin "2") (pinfunction "2_2") (pintype "passive"))
    )
    (net (code "20") (name "Net-(Q3-S)") (class "Default")
      (node (ref "Q3") (pin "2") (pinfunction "S_2") (pintype "passive"))
      (node (ref "R14") (pin "2") (pinfunction "2_2") (pintype "passive"))
      (node (ref "R16") (pin "2") (pinfunction "2_2") (pintype "passive"))
      (node (ref "R18") (pin "2") (pinfunction "2_2") (pintype "passive"))
    )
    (net (code "21") (name "Net-(Q4-D)") (class "Default")
      (node (ref "Q4") (pin "3") (pinfunction "D_3") (pintype "passive"))
      (node (ref "R19") (pin "2") (pinfunction "2_2") (pintype "passive"))
    )
    (net (code "22") (name "Net-(R10-Pad1)") (class "Default")
      (node (ref "R10") (pin "1") (pinfunction "1_1") (pintype "passive"))
      (node (ref "R11") (pin "2") (pinfunction "2_2") (pintype "passive"))
    )
    (net (code "23") (name "Net-(R10-Pad2)") (class "Default")
      (node (ref "R10") (pin "2") (pinfunction "2_2") (pintype "passive"))
      (node (ref "R7") (pin "1") (pinfunction "1_1") (pintype "passive"))
    )
    (net (code "24") (name "Net-(R26-Pad1)") (class "Default")
      (node (ref "R26") (pin "1") (pinfunction "1_1") (pintype "passive"))
      (node (ref "R28") (pin "3") (pinfunction "3_3") (pintype "passive"))
    )
    (net (code "25") (name "Net-(R28-Pad1)") (class "Default")
      (node (ref "R28") (pin "1") (pinfunction "1_1") (pintype "passive"))
      (node (ref "R29") (pin "2") (pinfunction "2_2") (pintype "passive"))
    )
    (net (code "26") (name "Net-(U2-AON)") (class "Default")
      (node (ref "R24") (pin "2") (pinfunction "2_2") (pintype "passive"))
      (node (ref "R31") (pin "2") (pinfunction "2_2") (pintype "passive"))
      (node (ref "R9") (pin "2") (pinfunction "2_2") (pintype "passive"))
      (node (ref "U2") (pin "6") (pinfunction "AON_6") (pintype "passive"))
    )
    (net (code "27") (name "Net-(U2-AOP)") (class "Default")
      (node (ref "R2") (pin "2") (pinfunction "2_2") (pintype "passive"))
      (node (ref "R30") (pin "2") (pinfunction "2_2") (pintype "passive"))
      (node (ref "R6") (pin "2") (pinfunction "2_2") (pintype "passive"))
      (node (ref "U2") (pin "7") (pinfunction "AOP_7") (pintype "passive"))
    )
    (net (code "28") (name "Net-(U3-1IN+)") (class "Default")
      (node (ref "C16") (pin "2") (pinfunction "2_2") (pintype "passive"))
      (node (ref "R2") (pin "1") (pinfunction "1_1") (pintype "passive"))
      (node (ref "R3") (pin "2") (pinfunction "2_2") (pintype "passive"))
      (node (ref "R30") (pin "1") (pinfunction "1_1") (pintype "passive"))
      (node (ref "R6") (pin "1") (pinfunction "1_1") (pintype "passive"))
      (node (ref "U3") (pin "3") (pinfunction "1IN+_3") (pintype "input"))
    )
    (net (code "29") (name "Net-(U3-1IN-)") (class "Default")
      (node (ref "C17") (pin "2") (pinfunction "2_2") (pintype "passive"))
      (node (ref "R20") (pin "2") (pinfunction "2_2") (pintype "passive"))
      (node (ref "R24") (pin "1") (pinfunction "1_1") (pintype "passive"))
      (node (ref "R31") (pin "1") (pinfunction "1_1") (pintype "passive"))
      (node (ref "R9") (pin "1") (pinfunction "1_1") (pintype "passive"))
      (node (ref "U3") (pin "4") (pinfunction "1IN-_4") (pintype "input"))
    )
    (net (code "30") (name "Net-(U3-1OUT)") (class "Default")
      (node (ref "C17") (pin "1") (pinfunction "1_1") (pintype "passive"))
      (node (ref "R13") (pin "1") (pinfunction "1_1") (pintype "passive"))
      (node (ref "R20") (pin "1") (pinfunction "1_1") (pintype "passive"))
      (node (ref "R32") (pin "2") (pinfunction "2_2") (pintype "passive"))
      (node (ref "U3") (pin "1") (pinfunction "1OUT_1") (pintype "output"))
    )
    (net (code "31") (name "Net-(U5-1IN+)") (class "Default")
      (node (ref "C4") (pin "2") (pinfunction "2_2") (pintype "passive"))
      (node (ref "R17") (pin "2") (pinfunction "2_2") (pintype "passive"))
      (node (ref "R22") (pin "1") (pinfunction "1_1") (pintype "passive"))
      (node (ref "U5") (pin "3") (pinfunction "1IN+_3") (pintype "input"))
    )
    (net (code "32") (name "Net-(U8-1IN+)") (class "Default")
      (node (ref "C28") (pin "2") (pinfunction "2_2") (pintype "passive"))
      (node (ref "R32") (pin "1") (pinfunction "1_1") (pintype "passive"))
      (node (ref "U8") (pin "3") (pinfunction "1IN+_3") (pintype "input"))
    )
    (net (code "33") (name "Net-(U8-1IN-)") (class "Default")
      (node (ref "C23") (pin "2") (pinfunction "2_2") (pintype "passive"))
      (node (ref "R14") (pin "1") (pinfunction "1_1") (pintype "passive"))
      (node (ref "R16") (pin "1") (pinfunction "1_1") (pintype "passive"))
      (node (ref "R18") (pin "1") (pinfunction "1_1") (pintype "passive"))
      (node (ref "R7") (pin "2") (pinfunction "2_2") (pintype "passive"))
      (node (ref "U8") (pin "4") (pinfunction "1IN-_4") (pintype "input"))
    )
    (net (code "34") (name "Net-(U8-1OUT)") (class "Default")
      (node (ref "C23") (pin "1") (pinfunction "1_1") (pintype "passive"))
      (node (ref "R11") (pin "1") (pinfunction "1_1") (pintype "passive"))
      (node (ref "R15") (pin "2") (pinfunction "2_2") (pintype "passive"))
      (node (ref "R4") (pin "2") (pinfunction "2_2") (pintype "passive"))
      (node (ref "R8") (pin "2") (pinfunction "2_2") (pintype "passive"))
      (node (ref "U8") (pin "1") (pinfunction "1OUT_1") (pintype "output"))
    )
  )
)
